# flashlightswitch.net
KiCad netlist of a schematic drawn in EAGLE
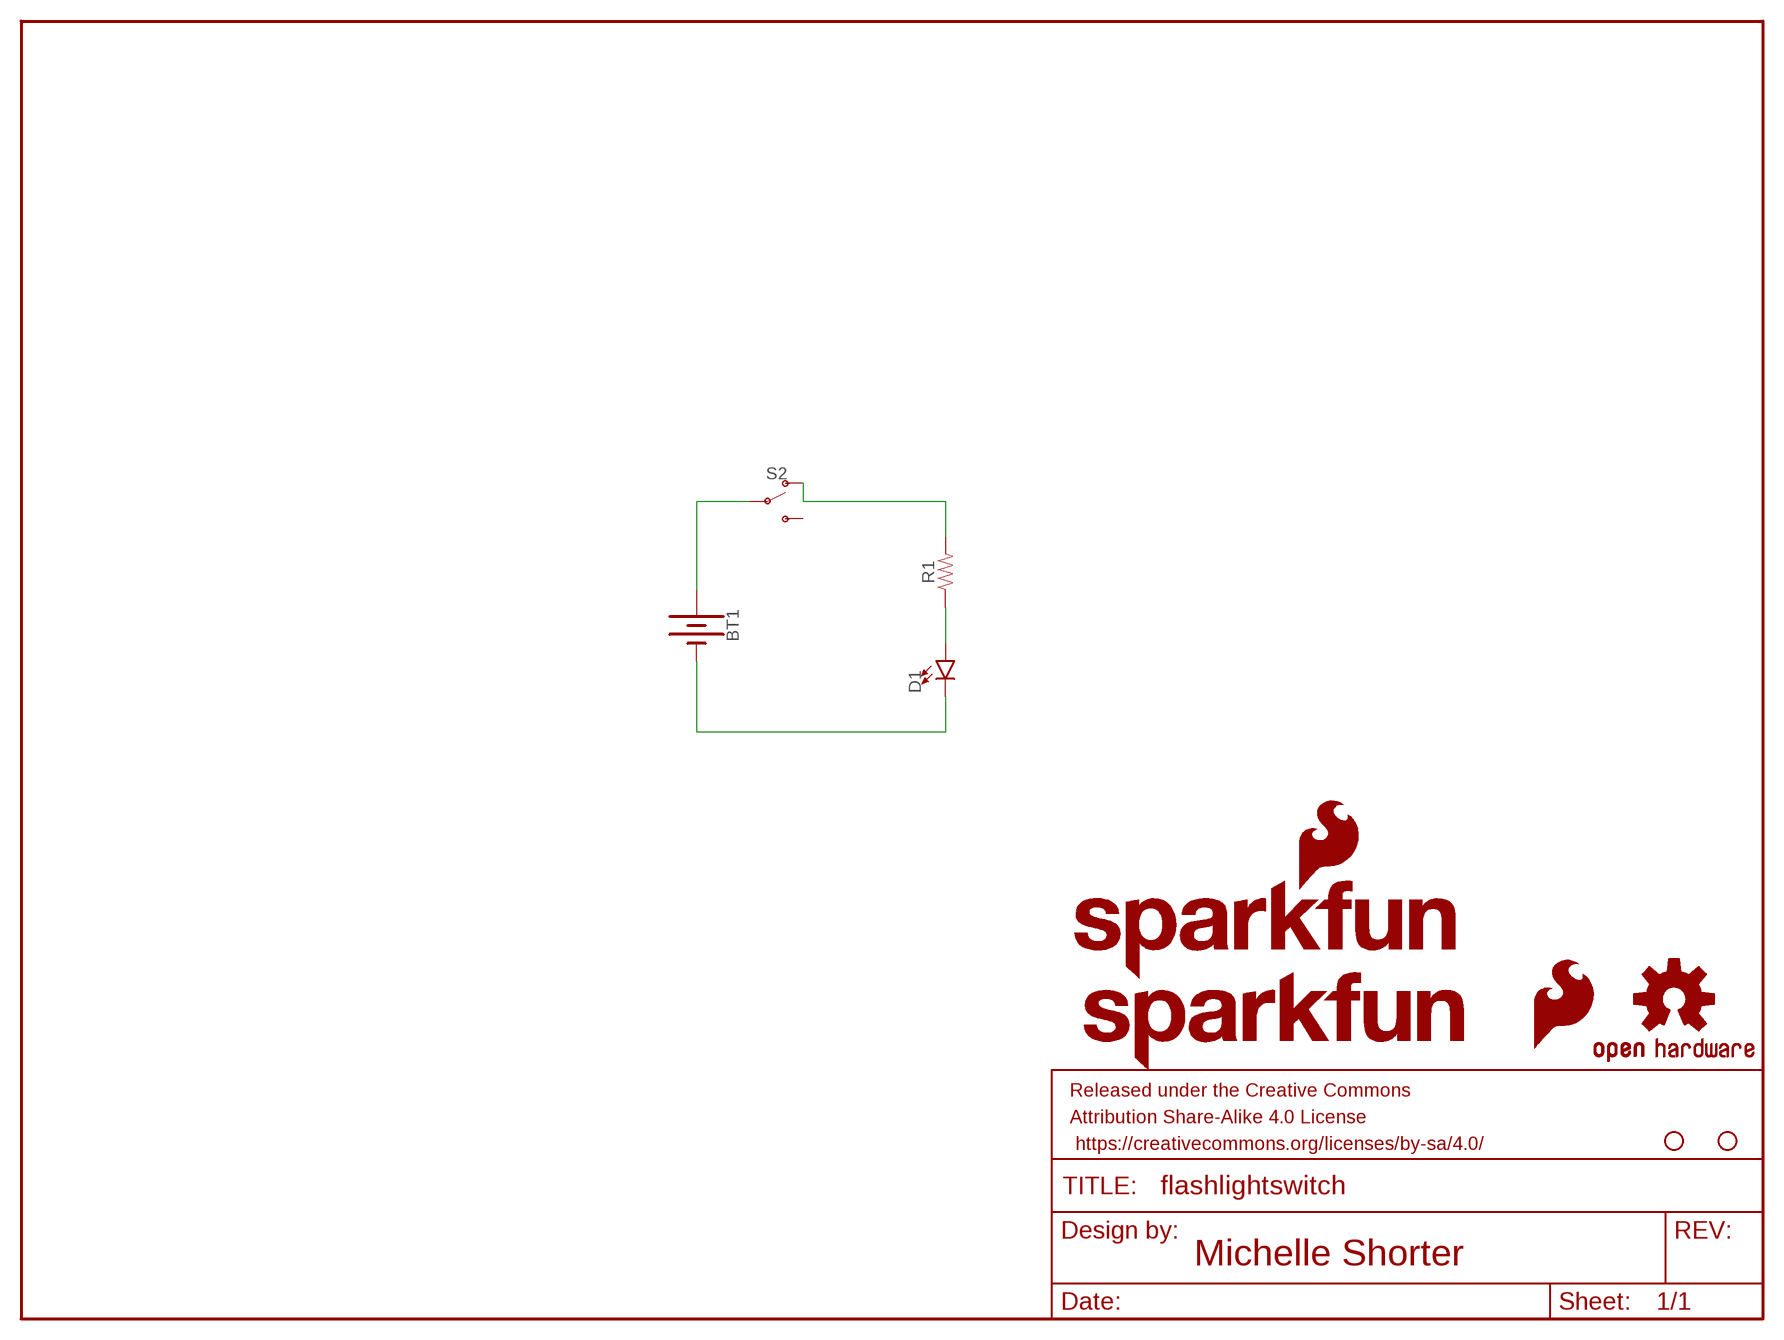
[diagram p0: schematic, sheet 1]

(export (version "E")
  (design (tool "Eeschema 10.0.6"))
  (components
    (comp (ref "BT1")
      (value "BATTERY-20MM_SMD")
      (footprint "eagle-import:BATTCON_20MM")
      (libsource (lib "eagle-import") (part "BATTERY-20MM_SMD"))
    )
    (comp (ref "D1")
      (value "LED5MM-KIT")
      (footprint "eagle-import:LED_5MM-KIT")
      (libsource (lib "eagle-import") (part "LED5MM-KIT"))
    )
    (comp (ref "FRAME1")
      (value "FRAME-LETTER")
      (footprint "eagle-import:CREATIVE_COMMONS")
      (libsource (lib "eagle-import") (part "FRAME-LETTER"))
    )
    (comp (ref "H1")
      (value "STAND-OFF")
      (footprint "eagle-import:STAND-OFF")
      (libsource (lib "eagle-import") (part "STAND-OFF"))
    )
    (comp (ref "H2")
      (value "STAND-OFF")
      (footprint "eagle-import:STAND-OFF")
      (libsource (lib "eagle-import") (part "STAND-OFF"))
    )
    (comp (ref "LOGO1")
      (value "OSHW-LOGOS")
      (footprint "eagle-import:OSHW-LOGO-S")
      (libsource (lib "eagle-import") (part "OSHW-LOGOS"))
    )
    (comp (ref "LOGO2")
      (value "SFE_LOGO_FLAME.1_INCH")
      (footprint "eagle-import:SFE_LOGO_FLAME_.1")
      (libsource (lib "eagle-import") (part "SFE_LOGO_FLAME.1_INCH"))
    )
    (comp (ref "LOGO3")
      (value "SFE_LOGO_NAME_FLAME.2_INCH")
      (footprint "eagle-import:SFE_LOGO_NAME_FLAME_.2")
      (libsource (lib "eagle-import") (part "SFE_LOGO_NAME_FLAME.2_INCH"))
    )
    (comp (ref "LOGO4")
      (value "SFE_LOGO_NAME.1_INCH")
      (footprint "eagle-import:SFE_LOGO_NAME_.1")
      (libsource (lib "eagle-import") (part "SFE_LOGO_NAME.1_INCH"))
    )
    (comp (ref "R1")
      (value "RESISTORAXIAL-0.3-KIT")
      (footprint "eagle-import:AXIAL-0.3-KIT")
      (libsource (lib "eagle-import") (part "RESISTORAXIAL-0.3-KIT"))
    )
    (comp (ref "S2")
      (value "SWITCH-SPDT-PTH-11.6X4.0MM-KIT")
      (footprint "eagle-import:SWITCH_SPDT_PTH_11.6X4.0MM_KIT")
      (libsource (lib "eagle-import") (part "SWITCH-SPDT-PTH-11.6X4.0MM-KIT"))
    )
  )
  (nets
    (net (code "1") (name "Net-(BT1-+)") (class "Default")
      (node (ref "BT1") (pin "1") (pinfunction "+_1") (pintype "power_in"))
      (node (ref "S2") (pin "2") (pinfunction "P_2") (pintype "passive"))
    )
    (net (code "2") (name "Net-(BT1--)") (class "Default")
      (node (ref "BT1") (pin "2") (pinfunction "-_2") (pintype "power_in"))
      (node (ref "D1") (pin "K") (pinfunction "C_K") (pintype "passive"))
    )
    (net (code "3") (name "Net-(R1-1)") (class "Default")
      (node (ref "D1") (pin "A") (pinfunction "A_A") (pintype "passive"))
      (node (ref "R1") (pin "P$1") (pinfunction "1_P$1") (pintype "passive"))
    )
    (net (code "4") (name "Net-(R1-2)") (class "Default")
      (node (ref "R1") (pin "P$2") (pinfunction "2_P$2") (pintype "passive"))
      (node (ref "S2") (pin "1") (pinfunction "O_1") (pintype "passive"))
    )
    (net (code "5") (name "unconnected-(S2-S-Pad3)") (class "Default")
      (node (ref "S2") (pin "3") (pinfunction "S_3") (pintype "passive"))
    )
  )
)
